# inv_sh_shoheil_74ls245.net
KiCad netlist of a schematic drawn in Altium Designer
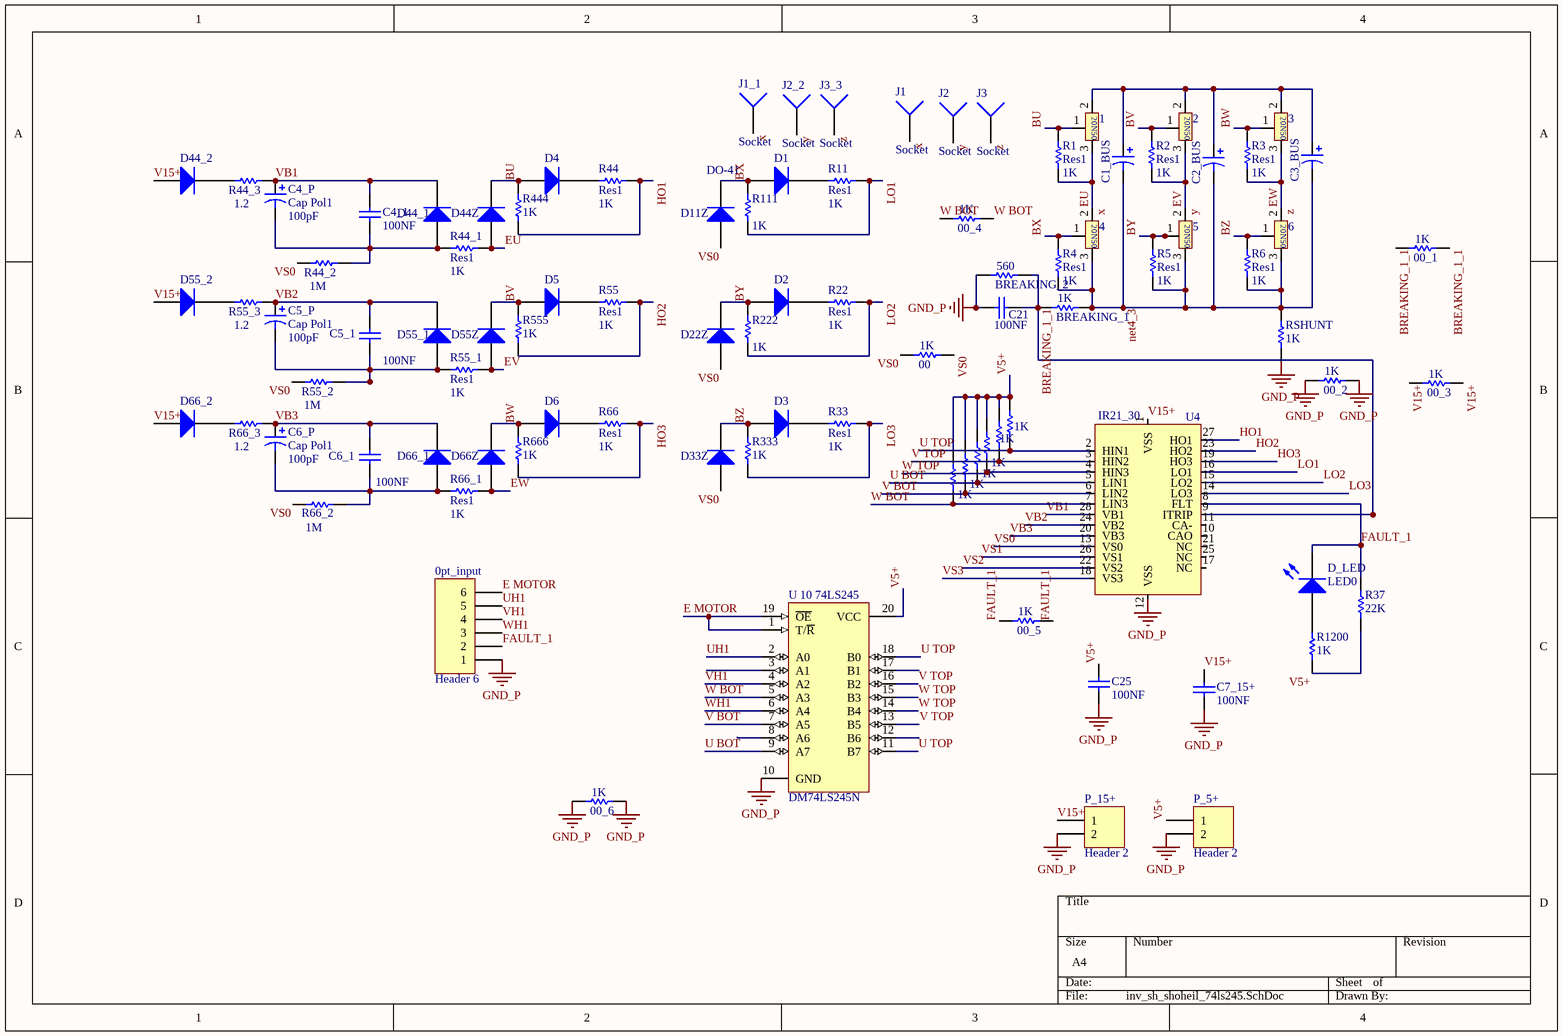
[diagram p0: inv_sh_shoheil_74ls245.SchDoc]

(export (version "E")
  (design (tool "Eeschema 10.0.6"))
  (components
    (comp (ref "00")
      (value "1K")
      (footprint "AXIAL-0.3")
      (description "Resistor")
      (fields (field (name "Comment") "Res1") (field (name "PUBLISHER") "Altium Limited"))
      (libsource (lib "Miscellaneous Devices") (part "Res1"))
    )
    (comp (ref "0pt_input")
      (value "Header 6")
      (footprint "HDR1X6")
      (description "Header, 6-Pin")
      (fields (field (name "PUBLISHER") "Altium Limited"))
      (libsource (lib "Miscellaneous Connectors") (part "Header 6"))
    )
    (comp (ref "00_1")
      (value "1K")
      (footprint "AXIAL-0.3")
      (description "Resistor")
      (fields (field (name "Comment") "Res1") (field (name "PUBLISHER") "Altium Limited"))
      (libsource (lib "Miscellaneous Devices") (part "Res1"))
    )
    (comp (ref "00_2")
      (value "1K")
      (footprint "AXIAL-0.3")
      (description "Resistor")
      (fields (field (name "Comment") "Res1") (field (name "PUBLISHER") "Altium Limited"))
      (libsource (lib "Miscellaneous Devices") (part "Res1"))
    )
    (comp (ref "00_3")
      (value "1K")
      (footprint "AXIAL-0.3")
      (description "Resistor")
      (fields (field (name "Comment") "Res1") (field (name "PUBLISHER") "Altium Limited"))
      (libsource (lib "Miscellaneous Devices") (part "Res1"))
    )
    (comp (ref "00_4")
      (value "1K")
      (footprint "AXIAL-0.3")
      (description "Resistor")
      (fields (field (name "Comment") "Res1") (field (name "PUBLISHER") "Altium Limited"))
      (libsource (lib "Miscellaneous Devices") (part "Res1"))
    )
    (comp (ref "00_5")
      (value "1K")
      (footprint "AXIAL-0.3")
      (description "Resistor")
      (fields (field (name "Comment") "Res1") (field (name "PUBLISHER") "Altium Limited"))
      (libsource (lib "Miscellaneous Devices") (part "Res1"))
    )
    (comp (ref "00_6")
      (value "1K")
      (footprint "AXIAL-0.3")
      (description "Resistor")
      (fields (field (name "Comment") "Res1") (field (name "PUBLISHER") "Altium Limited"))
      (libsource (lib "Miscellaneous Devices") (part "Res1"))
    )
    (comp (ref "1")
      (value "igbt_20n50")
      (footprint "20N50_S")
      (libsource (lib "INV_LIB_SH") (part "igbt_20n50"))
    )
    (comp (ref "2")
      (value "igbt_20n50")
      (footprint "20N50_S")
      (libsource (lib "INV_LIB_SH") (part "igbt_20n50"))
    )
    (comp (ref "3")
      (value "igbt_20n50")
      (footprint "20N50_S")
      (libsource (lib "INV_LIB_SH") (part "igbt_20n50"))
    )
    (comp (ref "4")
      (value "igbt_20n50")
      (footprint "20N50_S")
      (libsource (lib "INV_LIB_SH") (part "igbt_20n50"))
    )
    (comp (ref "5")
      (value "igbt_20n50")
      (footprint "20N50_S")
      (libsource (lib "INV_LIB_SH") (part "igbt_20n50"))
    )
    (comp (ref "6")
      (value "igbt_20n50")
      (footprint "20N50_S")
      (libsource (lib "INV_LIB_SH") (part "igbt_20n50"))
    )
    (comp (ref "BREAKING_1")
      (value "1K")
      (footprint "AXIAL-0.5")
      (description "Resistor")
      (fields (field (name "Comment") "Res1") (field (name "PUBLISHER") "Altium Limited"))
      (libsource (lib "Miscellaneous Devices") (part "Res1"))
    )
    (comp (ref "BREAKING_2")
      (value "560")
      (footprint "AXIAL-0.5")
      (description "Resistor")
      (fields (field (name "Comment") "Res1") (field (name "PUBLISHER") "Altium Limited"))
      (libsource (lib "Miscellaneous Devices") (part "Res1"))
    )
    (comp (ref "C1_BUS")
      (value "Cap Pol1")
      (footprint "RB7.6-15")
      (description "Polarized Capacitor (Radial)")
      (fields (field (name "PUBLISHER") "Altium Limited"))
      (libsource (lib "Miscellaneous Devices") (part "Cap Pol1"))
    )
    (comp (ref "C2_BUS")
      (value "Cap Pol1")
      (footprint "RB7.6-15")
      (description "Polarized Capacitor (Radial)")
      (fields (field (name "PUBLISHER") "Altium Limited"))
      (libsource (lib "Miscellaneous Devices") (part "Cap Pol1"))
    )
    (comp (ref "C3_BUS")
      (value "Cap Pol1")
      (footprint "RB7.6-15")
      (description "Polarized Capacitor (Radial)")
      (fields (field (name "PUBLISHER") "Altium Limited"))
      (libsource (lib "Miscellaneous Devices") (part "Cap Pol1"))
    )
    (comp (ref "C4_1")
      (value "100NF")
      (footprint "C2B")
      (description "Capacitor")
      (fields (field (name "Comment") "Cap") (field (name "PUBLISHER") "Altium Limited"))
      (libsource (lib "Miscellaneous Devices") (part "Cap"))
    )
    (comp (ref "C4_P")
      (value "Cap Pol1")
      (footprint "CE2")
      (description "Polarized Capacitor (Radial)")
      (fields (field (name "ALTIUM_VALUE") "100pF") (field (name "PUBLISHER") "Altium Limited"))
      (libsource (lib "Miscellaneous Devices") (part "Cap Pol1"))
    )
    (comp (ref "C5_1")
      (value "100NF")
      (footprint "C2B")
      (description "Capacitor")
      (fields (field (name "Comment") "Cap") (field (name "PUBLISHER") "Altium Limited"))
      (libsource (lib "Miscellaneous Devices") (part "Cap"))
    )
    (comp (ref "C5_P")
      (value "Cap Pol1")
      (footprint "CE2")
      (description "Polarized Capacitor (Radial)")
      (fields (field (name "ALTIUM_VALUE") "100pF") (field (name "PUBLISHER") "Altium Limited"))
      (libsource (lib "Miscellaneous Devices") (part "Cap Pol1"))
    )
    (comp (ref "C6_1")
      (value "100NF")
      (footprint "C2B")
      (description "Capacitor")
      (fields (field (name "Comment") "Cap") (field (name "PUBLISHER") "Altium Limited"))
      (libsource (lib "Miscellaneous Devices") (part "Cap"))
    )
    (comp (ref "C6_P")
      (value "Cap Pol1")
      (footprint "CE2")
      (description "Polarized Capacitor (Radial)")
      (fields (field (name "ALTIUM_VALUE") "100pF") (field (name "PUBLISHER") "Altium Limited"))
      (libsource (lib "Miscellaneous Devices") (part "Cap Pol1"))
    )
    (comp (ref "C7_15+")
      (value "100NF")
      (footprint "C2")
      (description "Capacitor")
      (fields (field (name "Comment") "Cap") (field (name "PUBLISHER") "Altium Limited"))
      (libsource (lib "Miscellaneous Devices") (part "Cap"))
    )
    (comp (ref "C21")
      (value "100NF")
      (footprint "C2")
      (description "Capacitor")
      (fields (field (name "Comment") "Cap") (field (name "PUBLISHER") "Altium Limited"))
      (libsource (lib "Miscellaneous Devices") (part "Cap"))
    )
    (comp (ref "C25")
      (value "100NF")
      (footprint "C2")
      (description "Capacitor")
      (fields (field (name "Comment") "Cap") (field (name "PUBLISHER") "Altium Limited"))
      (libsource (lib "Miscellaneous Devices") (part "Cap"))
    )
    (comp (ref "D1")
      (value "Diode 1N4007")
      (footprint "DIO10.46-5.3x2.8")
      (description "1 Amp General Purpose Rectifier")
      (fields (field (name "PUBLISHER") "Altium Limited"))
      (libsource (lib "Miscellaneous Devices") (part "Diode 1N4007"))
    )
    (comp (ref "D2")
      (value "Diode 1N4007")
      (footprint "DIO10.46-5.3x2.8")
      (description "1 Amp General Purpose Rectifier")
      (fields (field (name "PUBLISHER") "Altium Limited"))
      (libsource (lib "Miscellaneous Devices") (part "Diode 1N4007"))
    )
    (comp (ref "D3")
      (value "Diode 1N4007")
      (footprint "DIO10.46-5.3x2.8")
      (description "1 Amp General Purpose Rectifier")
      (fields (field (name "PUBLISHER") "Altium Limited"))
      (libsource (lib "Miscellaneous Devices") (part "Diode 1N4007"))
    )
    (comp (ref "D4")
      (value "Diode 1N4007")
      (footprint "DIO10.46-5.3x2.8")
      (description "1 Amp General Purpose Rectifier")
      (fields (field (name "PUBLISHER") "Altium Limited"))
      (libsource (lib "Miscellaneous Devices") (part "Diode 1N4007"))
    )
    (comp (ref "D5")
      (value "Diode 1N4007")
      (footprint "DIO10.46-5.3x2.8")
      (description "1 Amp General Purpose Rectifier")
      (fields (field (name "PUBLISHER") "Altium Limited"))
      (libsource (lib "Miscellaneous Devices") (part "Diode 1N4007"))
    )
    (comp (ref "D6")
      (value "Diode 1N4007")
      (footprint "DIO10.46-5.3x2.8")
      (description "1 Amp General Purpose Rectifier")
      (fields (field (name "PUBLISHER") "Altium Limited"))
      (libsource (lib "Miscellaneous Devices") (part "Diode 1N4007"))
    )
    (comp (ref "D11Z")
      (value "Diode 1N4007")
      (footprint "DIO10.46-5.3x2.8")
      (description "1 Amp General Purpose Rectifier")
      (fields (field (name "PACKAGEREFERENCE") "DO-41") (field (name "PUBLISHER") "Altium Limited"))
      (libsource (lib "Miscellaneous Devices") (part "Diode 1N4007"))
    )
    (comp (ref "D22Z")
      (value "Diode 1N4007")
      (footprint "DIO10.46-5.3x2.8")
      (description "1 Amp General Purpose Rectifier")
      (fields (field (name "PUBLISHER") "Altium Limited"))
      (libsource (lib "Miscellaneous Devices") (part "Diode 1N4007"))
    )
    (comp (ref "D33Z")
      (value "Diode 1N4007")
      (footprint "DIO10.46-5.3x2.8")
      (description "1 Amp General Purpose Rectifier")
      (fields (field (name "PUBLISHER") "Altium Limited"))
      (libsource (lib "Miscellaneous Devices") (part "Diode 1N4007"))
    )
    (comp (ref "D44Z")
      (value "Diode 1N4007")
      (footprint "DIO10.46-5.3x2.8")
      (description "1 Amp General Purpose Rectifier")
      (fields (field (name "PUBLISHER") "Altium Limited"))
      (libsource (lib "Miscellaneous Devices") (part "Diode 1N4007"))
    )
    (comp (ref "D44_1")
      (value "Diode 1N4007")
      (footprint "DIO10.46-5.3x2.8")
      (description "1 Amp General Purpose Rectifier")
      (fields (field (name "PUBLISHER") "Altium Limited"))
      (libsource (lib "Miscellaneous Devices") (part "Diode 1N4007"))
    )
    (comp (ref "D44_2")
      (value "Diode 1N4007")
      (footprint "DIO10.46-5.3x2.8")
      (description "1 Amp General Purpose Rectifier")
      (fields (field (name "PUBLISHER") "Altium Limited"))
      (libsource (lib "Miscellaneous Devices") (part "Diode 1N4007"))
    )
    (comp (ref "D55Z")
      (value "Diode 1N4007")
      (footprint "DIO10.46-5.3x2.8")
      (description "1 Amp General Purpose Rectifier")
      (fields (field (name "PUBLISHER") "Altium Limited"))
      (libsource (lib "Miscellaneous Devices") (part "Diode 1N4007"))
    )
    (comp (ref "D55_1")
      (value "Diode 1N4007")
      (footprint "DIO10.46-5.3x2.8")
      (description "1 Amp General Purpose Rectifier")
      (fields (field (name "PUBLISHER") "Altium Limited"))
      (libsource (lib "Miscellaneous Devices") (part "Diode 1N4007"))
    )
    (comp (ref "D55_2")
      (value "Diode 1N4007")
      (footprint "DIO10.46-5.3x2.8")
      (description "1 Amp General Purpose Rectifier")
      (fields (field (name "PUBLISHER") "Altium Limited"))
      (libsource (lib "Miscellaneous Devices") (part "Diode 1N4007"))
    )
    (comp (ref "D66Z")
      (value "Diode 1N4007")
      (footprint "DIO10.46-5.3x2.8")
      (description "1 Amp General Purpose Rectifier")
      (fields (field (name "PUBLISHER") "Altium Limited"))
      (libsource (lib "Miscellaneous Devices") (part "Diode 1N4007"))
    )
    (comp (ref "D66_1")
      (value "Diode 1N4007")
      (footprint "DIO10.46-5.3x2.8")
      (description "1 Amp General Purpose Rectifier")
      (fields (field (name "PUBLISHER") "Altium Limited"))
      (libsource (lib "Miscellaneous Devices") (part "Diode 1N4007"))
    )
    (comp (ref "D66_2")
      (value "Diode 1N4007")
      (footprint "DIO10.46-5.3x2.8")
      (description "1 Amp General Purpose Rectifier")
      (fields (field (name "PUBLISHER") "Altium Limited"))
      (libsource (lib "Miscellaneous Devices") (part "Diode 1N4007"))
    )
    (comp (ref "D_LED")
      (value "LED0")
      (footprint "CE5")
      (description "Typical INFRARED GaAs LED")
      (fields (field (name "PUBLISHER") "Altium Limited"))
      (libsource (lib "Miscellaneous Devices") (part "LED0"))
    )
    (comp (ref "J1")
      (value "Socket")
      (footprint "PIN1")
      (fields (field (name "PUBLISHER") "Altium Limited"))
      (libsource (lib "Miscellaneous Connectors") (part "Socket"))
    )
    (comp (ref "J1_1")
      (value "Socket")
      (footprint "PIN1")
      (fields (field (name "PUBLISHER") "Altium Limited"))
      (libsource (lib "Miscellaneous Connectors") (part "Socket"))
    )
    (comp (ref "J2")
      (value "Socket")
      (footprint "PIN1")
      (fields (field (name "PUBLISHER") "Altium Limited"))
      (libsource (lib "Miscellaneous Connectors") (part "Socket"))
    )
    (comp (ref "J2_2")
      (value "Socket")
      (footprint "PIN1")
      (fields (field (name "PUBLISHER") "Altium Limited"))
      (libsource (lib "Miscellaneous Connectors") (part "Socket"))
    )
    (comp (ref "J3")
      (value "Socket")
      (footprint "PIN1")
      (fields (field (name "PUBLISHER") "Altium Limited"))
      (libsource (lib "Miscellaneous Connectors") (part "Socket"))
    )
    (comp (ref "J3_3")
      (value "Socket")
      (footprint "PIN1")
      (fields (field (name "PUBLISHER") "Altium Limited"))
      (libsource (lib "Miscellaneous Connectors") (part "Socket"))
    )
    (comp (ref "P_5+")
      (value "Header 2")
      (footprint "HDR1X2")
      (description "Header, 2-Pin")
      (fields (field (name "PUBLISHER") "Altium Limited"))
      (libsource (lib "Miscellaneous Connectors") (part "Header 2"))
    )
    (comp (ref "P_15+")
      (value "Header 2")
      (footprint "HDR1X2")
      (description "Header, 2-Pin")
      (fields (field (name "PUBLISHER") "Altium Limited"))
      (libsource (lib "Miscellaneous Connectors") (part "Header 2"))
    )
    (comp (ref "R1")
      (value "Res1")
      (footprint "AXIAL-0.3")
      (description "Resistor")
      (fields (field (name "ALTIUM_VALUE") "1K") (field (name "PUBLISHER") "Altium Limited"))
      (libsource (lib "Miscellaneous Devices") (part "Res1"))
    )
    (comp (ref "R2")
      (value "Res1")
      (footprint "AXIAL-0.3")
      (description "Resistor")
      (fields (field (name "ALTIUM_VALUE") "1K") (field (name "PUBLISHER") "Altium Limited"))
      (libsource (lib "Miscellaneous Devices") (part "Res1"))
    )
    (comp (ref "R3")
      (value "Res1")
      (footprint "AXIAL-0.3")
      (description "Resistor")
      (fields (field (name "ALTIUM_VALUE") "1K") (field (name "PUBLISHER") "Altium Limited"))
      (libsource (lib "Miscellaneous Devices") (part "Res1"))
    )
    (comp (ref "R4")
      (value "Res1")
      (footprint "AXIAL-0.3")
      (description "Resistor")
      (fields (field (name "ALTIUM_VALUE") "1K") (field (name "PUBLISHER") "Altium Limited"))
      (libsource (lib "Miscellaneous Devices") (part "Res1"))
    )
    (comp (ref "R5")
      (value "Res1")
      (footprint "AXIAL-0.3")
      (description "Resistor")
      (fields (field (name "ALTIUM_VALUE") "1K") (field (name "PUBLISHER") "Altium Limited"))
      (libsource (lib "Miscellaneous Devices") (part "Res1"))
    )
    (comp (ref "R6")
      (value "Res1")
      (footprint "AXIAL-0.3")
      (description "Resistor")
      (fields (field (name "ALTIUM_VALUE") "1K") (field (name "PUBLISHER") "Altium Limited"))
      (libsource (lib "Miscellaneous Devices") (part "Res1"))
    )
    (comp (ref "R11")
      (value "Res1")
      (footprint "AXIAL-0.3")
      (description "Resistor")
      (fields (field (name "ALTIUM_VALUE") "1K") (field (name "PUBLISHER") "Altium Limited"))
      (libsource (lib "Miscellaneous Devices") (part "Res1"))
    )
    (comp (ref "R22")
      (value "Res1")
      (footprint "AXIAL-0.3")
      (description "Resistor")
      (fields (field (name "ALTIUM_VALUE") "1K") (field (name "PUBLISHER") "Altium Limited"))
      (libsource (lib "Miscellaneous Devices") (part "Res1"))
    )
    (comp (ref "R33")
      (value "Res1")
      (footprint "AXIAL-0.3")
      (description "Resistor")
      (fields (field (name "ALTIUM_VALUE") "1K") (field (name "PUBLISHER") "Altium Limited"))
      (libsource (lib "Miscellaneous Devices") (part "Res1"))
    )
    (comp (ref "R37")
      (value "22K")
      (footprint "AXIAL-0.3")
      (description "Resistor")
      (fields (field (name "Comment") "Res1") (field (name "PUBLISHER") "Altium Limited"))
      (libsource (lib "Miscellaneous Devices") (part "Res1"))
    )
    (comp (ref "R44")
      (value "Res1")
      (footprint "AXIAL-0.3")
      (description "Resistor")
      (fields (field (name "ALTIUM_VALUE") "1K") (field (name "PUBLISHER") "Altium Limited"))
      (libsource (lib "Miscellaneous Devices") (part "Res1"))
    )
    (comp (ref "R44_1")
      (value "Res1")
      (footprint "AXIAL-0.3")
      (description "Resistor")
      (fields (field (name "ALTIUM_VALUE") "1K") (field (name "PUBLISHER") "Altium Limited"))
      (libsource (lib "Miscellaneous Devices") (part "Res1"))
    )
    (comp (ref "R44_2")
      (value "1M")
      (footprint "AXIAL-0.3")
      (description "Resistor")
      (fields (field (name "Comment") "Res1") (field (name "PUBLISHER") "Altium Limited"))
      (libsource (lib "Miscellaneous Devices") (part "Res1"))
    )
    (comp (ref "R44_3")
      (value "1.2")
      (footprint "AXIAL-0.3")
      (description "Resistor")
      (fields (field (name "Comment") "Res1") (field (name "PUBLISHER") "Altium Limited"))
      (libsource (lib "Miscellaneous Devices") (part "Res1"))
    )
    (comp (ref "R47_1")
      (value "1K")
      (footprint "AXIAL-0.3")
      (description "Resistor")
      (fields (field (name "Comment") "Res1") (field (name "PUBLISHER") "Altium Limited"))
      (libsource (lib "Miscellaneous Devices") (part "Res1"))
    )
    (comp (ref "R47_2")
      (value "1K")
      (footprint "AXIAL-0.3")
      (description "Resistor")
      (fields (field (name "Comment") "Res1") (field (name "PUBLISHER") "Altium Limited"))
      (libsource (lib "Miscellaneous Devices") (part "Res1"))
    )
    (comp (ref "R47_3")
      (value "1K")
      (footprint "AXIAL-0.3")
      (description "Resistor")
      (fields (field (name "Comment") "Res1") (field (name "PUBLISHER") "Altium Limited"))
      (libsource (lib "Miscellaneous Devices") (part "Res1"))
    )
    (comp (ref "R47_4")
      (value "1K")
      (footprint "AXIAL-0.3")
      (description "Resistor")
      (fields (field (name "Comment") "Res1") (field (name "PUBLISHER") "Altium Limited"))
      (libsource (lib "Miscellaneous Devices") (part "Res1"))
    )
    (comp (ref "R47_5")
      (value "1K")
      (footprint "AXIAL-0.3")
      (description "Resistor")
      (fields (field (name "Comment") "Res1") (field (name "PUBLISHER") "Altium Limited"))
      (libsource (lib "Miscellaneous Devices") (part "Res1"))
    )
    (comp (ref "R47_6")
      (value "1K")
      (footprint "AXIAL-0.3")
      (description "Resistor")
      (fields (field (name "Comment") "Res1") (field (name "PUBLISHER") "Altium Limited"))
      (libsource (lib "Miscellaneous Devices") (part "Res1"))
    )
    (comp (ref "R55")
      (value "Res1")
      (footprint "AXIAL-0.3")
      (description "Resistor")
      (fields (field (name "ALTIUM_VALUE") "1K") (field (name "PUBLISHER") "Altium Limited"))
      (libsource (lib "Miscellaneous Devices") (part "Res1"))
    )
    (comp (ref "R55_1")
      (value "Res1")
      (footprint "AXIAL-0.3")
      (description "Resistor")
      (fields (field (name "ALTIUM_VALUE") "1K") (field (name "PUBLISHER") "Altium Limited"))
      (libsource (lib "Miscellaneous Devices") (part "Res1"))
    )
    (comp (ref "R55_2")
      (value "1M")
      (footprint "AXIAL-0.3")
      (description "Resistor")
      (fields (field (name "Comment") "Res1") (field (name "PUBLISHER") "Altium Limited"))
      (libsource (lib "Miscellaneous Devices") (part "Res1"))
    )
    (comp (ref "R55_3")
      (value "1.2")
      (footprint "AXIAL-0.3")
      (description "Resistor")
      (fields (field (name "Comment") "Res1") (field (name "PUBLISHER") "Altium Limited"))
      (libsource (lib "Miscellaneous Devices") (part "Res1"))
    )
    (comp (ref "R66")
      (value "Res1")
      (footprint "AXIAL-0.3")
      (description "Resistor")
      (fields (field (name "ALTIUM_VALUE") "1K") (field (name "PUBLISHER") "Altium Limited"))
      (libsource (lib "Miscellaneous Devices") (part "Res1"))
    )
    (comp (ref "R66_1")
      (value "Res1")
      (footprint "AXIAL-0.3")
      (description "Resistor")
      (fields (field (name "ALTIUM_VALUE") "1K") (field (name "PUBLISHER") "Altium Limited"))
      (libsource (lib "Miscellaneous Devices") (part "Res1"))
    )
    (comp (ref "R66_2")
      (value "1M")
      (footprint "AXIAL-0.3")
      (description "Resistor")
      (fields (field (name "Comment") "Res1") (field (name "PUBLISHER") "Altium Limited"))
      (libsource (lib "Miscellaneous Devices") (part "Res1"))
    )
    (comp (ref "R66_3")
      (value "1.2")
      (footprint "AXIAL-0.3")
      (description "Resistor")
      (fields (field (name "Comment") "Res1") (field (name "PUBLISHER") "Altium Limited"))
      (libsource (lib "Miscellaneous Devices") (part "Res1"))
    )
    (comp (ref "R111")
      (value "1K")
      (footprint "AXIAL-0.3")
      (description "Resistor")
      (fields (field (name "Comment") "Res1") (field (name "PUBLISHER") "Altium Limited"))
      (libsource (lib "Miscellaneous Devices") (part "Res1"))
    )
    (comp (ref "R222")
      (value "1K")
      (footprint "AXIAL-0.3")
      (description "Resistor")
      (fields (field (name "Comment") "Res1") (field (name "PUBLISHER") "Altium Limited"))
      (libsource (lib "Miscellaneous Devices") (part "Res1"))
    )
    (comp (ref "R333")
      (value "1K")
      (footprint "AXIAL-0.3")
      (description "Resistor")
      (fields (field (name "Comment") "Res1") (field (name "PUBLISHER") "Altium Limited"))
      (libsource (lib "Miscellaneous Devices") (part "Res1"))
    )
    (comp (ref "R444")
      (value "1K")
      (footprint "AXIAL-0.3")
      (description "Resistor")
      (fields (field (name "Comment") "Res1") (field (name "PUBLISHER") "Altium Limited"))
      (libsource (lib "Miscellaneous Devices") (part "Res1"))
    )
    (comp (ref "R555")
      (value "1K")
      (footprint "AXIAL-0.3")
      (description "Resistor")
      (fields (field (name "Comment") "Res1") (field (name "PUBLISHER") "Altium Limited"))
      (libsource (lib "Miscellaneous Devices") (part "Res1"))
    )
    (comp (ref "R666")
      (value "1K")
      (footprint "AXIAL-0.3")
      (description "Resistor")
      (fields (field (name "Comment") "Res1") (field (name "PUBLISHER") "Altium Limited"))
      (libsource (lib "Miscellaneous Devices") (part "Res1"))
    )
    (comp (ref "R1200")
      (value "1K")
      (footprint "AXIAL-0.3")
      (description "Resistor")
      (fields (field (name "Comment") "Res1") (field (name "PUBLISHER") "Altium Limited"))
      (libsource (lib "Miscellaneous Devices") (part "Res1"))
    )
    (comp (ref "RSHUNT")
      (value "1K")
      (footprint "AXIAL-1.0")
      (description "Resistor")
      (fields (field (name "Comment") "Res1") (field (name "PUBLISHER") "Altium Limited"))
      (libsource (lib "Miscellaneous Devices") (part "Res1"))
    )
    (comp (ref "U 10 74LS245")
      (value "DM74LS245N")
      (footprint "N20A")
      (description "3-State Octal Bus Transceiver")
      (fields (field (name "PUBLISHER") "Altium Limited"))
      (libsource (lib "FSC Interface Line Transceiver") (part "DM74LS245N"))
    )
    (comp (ref "U4") (value "IR21_30") (footprint "IR2130") (libsource (lib "IR2130_SH") (part "IR21_30")))
  )
  (nets
    (net (code "1") (name "/BREAKING_1_1") (class "Default")
      (node (ref "00_1") (pin "1") (pinfunction "1_1") (pintype "passive"))
      (node (ref "00_1") (pin "2") (pinfunction "2_2") (pintype "passive"))
      (node (ref "BREAKING_1") (pin "1") (pinfunction "1_1") (pintype "passive"))
      (node (ref "BREAKING_2") (pin "2") (pinfunction "2_2") (pintype "passive"))
      (node (ref "C21") (pin "1") (pinfunction "1_1") (pintype "passive"))
      (node (ref "U4") (pin "9") (pinfunction "ITRIP_9") (pintype "passive"))
    )
    (net (code "2") (name "/BU") (class "Default")
      (node (ref "1") (pin "1") (pinfunction "G_1") (pintype "passive"))
      (node (ref "D4") (pin "1") (pinfunction "A_1") (pintype "passive"))
      (node (ref "D44Z") (pin "2") (pinfunction "K_2") (pintype "passive"))
      (node (ref "R1") (pin "2") (pinfunction "2_2") (pintype "passive"))
      (node (ref "R444") (pin "2") (pinfunction "2_2") (pintype "passive"))
    )
    (net (code "3") (name "/BV") (class "Default")
      (node (ref "2") (pin "1") (pinfunction "G_1") (pintype "passive"))
      (node (ref "D5") (pin "1") (pinfunction "A_1") (pintype "passive"))
      (node (ref "D55Z") (pin "2") (pinfunction "K_2") (pintype "passive"))
      (node (ref "R2") (pin "2") (pinfunction "2_2") (pintype "passive"))
      (node (ref "R555") (pin "2") (pinfunction "2_2") (pintype "passive"))
    )
    (net (code "4") (name "/BW") (class "Default")
      (node (ref "3") (pin "1") (pinfunction "G_1") (pintype "passive"))
      (node (ref "D6") (pin "1") (pinfunction "A_1") (pintype "passive"))
      (node (ref "D66Z") (pin "2") (pinfunction "K_2") (pintype "passive"))
      (node (ref "R3") (pin "2") (pinfunction "2_2") (pintype "passive"))
      (node (ref "R666") (pin "2") (pinfunction "2_2") (pintype "passive"))
    )
    (net (code "5") (name "/BX") (class "Default")
      (node (ref "4") (pin "1") (pinfunction "G_1") (pintype "passive"))
      (node (ref "D1") (pin "1") (pinfunction "A_1") (pintype "passive"))
      (node (ref "D11Z") (pin "2") (pinfunction "K_2") (pintype "passive"))
      (node (ref "R111") (pin "2") (pinfunction "2_2") (pintype "passive"))
      (node (ref "R4") (pin "2") (pinfunction "2_2") (pintype "passive"))
    )
    (net (code "6") (name "/BY") (class "Default")
      (node (ref "5") (pin "1") (pinfunction "G_1") (pintype "passive"))
      (node (ref "D2") (pin "1") (pinfunction "A_1") (pintype "passive"))
      (node (ref "D22Z") (pin "2") (pinfunction "K_2") (pintype "passive"))
      (node (ref "R222") (pin "2") (pinfunction "2_2") (pintype "passive"))
      (node (ref "R5") (pin "2") (pinfunction "2_2") (pintype "passive"))
    )
    (net (code "7") (name "/BZ") (class "Default")
      (node (ref "6") (pin "1") (pinfunction "G_1") (pintype "passive"))
      (node (ref "D3") (pin "1") (pinfunction "A_1") (pintype "passive"))
      (node (ref "D33Z") (pin "2") (pinfunction "K_2") (pintype "passive"))
      (node (ref "R333") (pin "2") (pinfunction "2_2") (pintype "passive"))
      (node (ref "R6") (pin "2") (pinfunction "2_2") (pintype "passive"))
    )
    (net (code "8") (name "/E MOTOR") (class "Default")
      (node (ref "0pt_input") (pin "6") (pinfunction "6_6") (pintype "passive"))
      (node (ref "U 10 74LS245") (pin "1") (pinfunction "T/~{R}_1") (pintype "input"))
      (node (ref "U 10 74LS245") (pin "19") (pinfunction "~{OE}_19") (pintype "input"))
    )
    (net (code "9") (name "/EU") (class "Default")
      (node (ref "1") (pin "3") (pinfunction "E_3") (pintype "passive"))
      (node (ref "4") (pin "2") (pinfunction "C_2") (pintype "passive"))
      (node (ref "D44Z") (pin "1") (pinfunction "A_1") (pintype "passive"))
      (node (ref "J1") (pin "1") (pinfunction "1_1") (pintype "passive"))
      (node (ref "J1_1") (pin "1") (pinfunction "1_1") (pintype "passive"))
      (node (ref "R1") (pin "1") (pinfunction "1_1") (pintype "passive"))
      (node (ref "R44_1") (pin "2") (pinfunction "2_2") (pintype "passive"))
    )
    (net (code "10") (name "/EV") (class "Default")
      (node (ref "2") (pin "3") (pinfunction "E_3") (pintype "passive"))
      (node (ref "5") (pin "2") (pinfunction "C_2") (pintype "passive"))
      (node (ref "D55Z") (pin "1") (pinfunction "A_1") (pintype "passive"))
      (node (ref "J2") (pin "1") (pinfunction "1_1") (pintype "passive"))
      (node (ref "J2_2") (pin "1") (pinfunction "1_1") (pintype "passive"))
      (node (ref "R2") (pin "1") (pinfunction "1_1") (pintype "passive"))
      (node (ref "R55_1") (pin "2") (pinfunction "2_2") (pintype "passive"))
    )
    (net (code "11") (name "/EW") (class "Default")
      (node (ref "3") (pin "3") (pinfunction "E_3") (pintype "passive"))
      (node (ref "6") (pin "2") (pinfunction "C_2") (pintype "passive"))
      (node (ref "D66Z") (pin "1") (pinfunction "A_1") (pintype "passive"))
      (node (ref "J3") (pin "1") (pinfunction "1_1") (pintype "passive"))
      (node (ref "J3_3") (pin "1") (pinfunction "1_1") (pintype "passive"))
      (node (ref "R3") (pin "1") (pinfunction "1_1") (pintype "passive"))
      (node (ref "R66_1") (pin "2") (pinfunction "2_2") (pintype "passive"))
    )
    (net (code "12") (name "/FAULT_1") (class "Default")
      (node (ref "00_5") (pin "1") (pinfunction "1_1") (pintype "passive"))
      (node (ref "00_5") (pin "2") (pinfunction "2_2") (pintype "passive"))
      (node (ref "0pt_input") (pin "2") (pinfunction "2_2") (pintype "passive"))
      (node (ref "D_LED") (pin "2") (pinfunction "K_2") (pintype "passive"))
      (node (ref "R37") (pin "2") (pinfunction "2_2") (pintype "passive"))
      (node (ref "U4") (pin "8") (pinfunction "FLT_8") (pintype "passive"))
    )
    (net (code "13") (name "/HO1") (class "Default")
      (node (ref "R44") (pin "2") (pinfunction "2_2") (pintype "passive"))
      (node (ref "R444") (pin "1") (pinfunction "1_1") (pintype "passive"))
      (node (ref "U4") (pin "27") (pinfunction "HO1_27") (pintype "passive"))
    )
    (net (code "14") (name "/HO2") (class "Default")
      (node (ref "R55") (pin "2") (pinfunction "2_2") (pintype "passive"))
      (node (ref "R555") (pin "1") (pinfunction "1_1") (pintype "passive"))
      (node (ref "U4") (pin "23") (pinfunction "HO2_23") (pintype "passive"))
    )
    (net (code "15") (name "/HO3") (class "Default")
      (node (ref "R66") (pin "2") (pinfunction "2_2") (pintype "passive"))
      (node (ref "R666") (pin "1") (pinfunction "1_1") (pintype "passive"))
      (node (ref "U4") (pin "19") (pinfunction "HO3_19") (pintype "passive"))
    )
    (net (code "16") (name "/LO1") (class "Default")
      (node (ref "R11") (pin "2") (pinfunction "2_2") (pintype "passive"))
      (node (ref "R111") (pin "1") (pinfunction "1_1") (pintype "passive"))
      (node (ref "U4") (pin "16") (pinfunction "LO1_16") (pintype "passive"))
    )
    (net (code "17") (name "/LO2") (class "Default")
      (node (ref "R22") (pin "2") (pinfunction "2_2") (pintype "passive"))
      (node (ref "R222") (pin "1") (pinfunction "1_1") (pintype "passive"))
      (node (ref "U4") (pin "15") (pinfunction "LO2_15") (pintype "passive"))
    )
    (net (code "18") (name "/LO3") (class "Default")
      (node (ref "R33") (pin "2") (pinfunction "2_2") (pintype "passive"))
      (node (ref "R333") (pin "1") (pinfunction "1_1") (pintype "passive"))
      (node (ref "U4") (pin "14") (pinfunction "LO3_14") (pintype "passive"))
    )
    (net (code "19") (name "/U BOT") (class "Default")
      (node (ref "R47_4") (pin "2") (pinfunction "2_2") (pintype "passive"))
      (node (ref "U 10 74LS245") (pin "9") (pinfunction "A7_9") (pintype "bidirectional"))
      (node (ref "U4") (pin "5") (pinfunction "LIN1_5") (pintype "passive"))
    )
    (net (code "20") (name "/U TOP") (class "Default")
      (node (ref "R47_1") (pin "2") (pinfunction "2_2") (pintype "passive"))
      (node (ref "U 10 74LS245") (pin "11") (pinfunction "B7_11") (pintype "bidirectional"))
      (node (ref "U 10 74LS245") (pin "18") (pinfunction "B0_18") (pintype "bidirectional"))
      (node (ref "U4") (pin "2") (pinfunction "HIN1_2") (pintype "passive"))
    )
    (net (code "21") (name "/UH1") (class "Default")
      (node (ref "0pt_input") (pin "5") (pinfunction "5_5") (pintype "passive"))
      (node (ref "U 10 74LS245") (pin "2") (pinfunction "A0_2") (pintype "bidirectional"))
    )
    (net (code "22") (name "/V BOT") (class "Default")
      (node (ref "R47_5") (pin "2") (pinfunction "2_2") (pintype "passive"))
      (node (ref "U 10 74LS245") (pin "7") (pinfunction "A5_7") (pintype "bidirectional"))
      (node (ref "U4") (pin "6") (pinfunction "LIN2_6") (pintype "passive"))
    )
    (net (code "23") (name "/V TOP") (class "Default")
      (node (ref "R47_2") (pin "2") (pinfunction "2_2") (pintype "passive"))
      (node (ref "U 10 74LS245") (pin "13") (pinfunction "B5_13") (pintype "bidirectional"))
      (node (ref "U 10 74LS245") (pin "16") (pinfunction "B2_16") (pintype "bidirectional"))
      (node (ref "U4") (pin "3") (pinfunction "HIN2_3") (pintype "passive"))
    )
    (net (code "24") (name "/V5+") (class "Default")
      (node (ref "C25") (pin "1") (pinfunction "1_1") (pintype "passive"))
      (node (ref "P_5+") (pin "1") (pinfunction "1_1") (pintype "passive"))
      (node (ref "R1200") (pin "1") (pinfunction "1_1") (pintype "passive"))
      (node (ref "R37") (pin "1") (pinfunction "1_1") (pintype "passive"))
      (node (ref "R47_1") (pin "1") (pinfunction "1_1") (pintype "passive"))
      (node (ref "R47_2") (pin "1") (pinfunction "1_1") (pintype "passive"))
      (node (ref "R47_3") (pin "1") (pinfunction "1_1") (pintype "passive"))
      (node (ref "R47_4") (pin "1") (pinfunction "1_1") (pintype "passive"))
      (node (ref "R47_5") (pin "1") (pinfunction "1_1") (pintype "passive"))
      (node (ref "R47_6") (pin "1") (pinfunction "1_1") (pintype "passive"))
      (node (ref "U 10 74LS245") (pin "20") (pinfunction "VCC_20") (pintype "power_in"))
    )
    (net (code "25") (name "/V15+") (class "Default")
      (node (ref "00_3") (pin "1") (pinfunction "1_1") (pintype "passive"))
      (node (ref "00_3") (pin "2") (pinfunction "2_2") (pintype "passive"))
      (node (ref "C7_15+") (pin "1") (pinfunction "1_1") (pintype "passive"))
      (node (ref "D44_2") (pin "1") (pinfunction "A_1") (pintype "passive"))
      (node (ref "D55_2") (pin "1") (pinfunction "A_1") (pintype "passive"))
      (node (ref "D66_2") (pin "1") (pinfunction "A_1") (pintype "passive"))
      (node (ref "P_15+") (pin "1") (pinfunction "1_1") (pintype "passive"))
      (node (ref "U4") (pin "1") (pinfunction "VSS_1") (pintype "passive"))
    )
    (net (code "26") (name "/VB1") (class "Default")
      (node (ref "C4_1") (pin "2") (pinfunction "2_2") (pintype "passive"))
      (node (ref "C4_P") (pin "1") (pinfunction "1_1") (pintype "passive"))
      (node (ref "D44_1") (pin "2") (pinfunction "K_2") (pintype "passive"))
      (node (ref "R44_3") (pin "2") (pinfunction "2_2") (pintype "passive"))
      (node (ref "U4") (pin "28") (pinfunction "VB1_28") (pintype "passive"))
    )
    (net (code "27") (name "/VB2") (class "Default")
      (node (ref "C5_1") (pin "2") (pinfunction "2_2") (pintype "passive"))
      (node (ref "C5_P") (pin "1") (pinfunction "1_1") (pintype "passive"))
      (node (ref "D55_1") (pin "2") (pinfunction "K_2") (pintype "passive"))
      (node (ref "R55_3") (pin "2") (pinfunction "2_2") (pintype "passive"))
      (node (ref "U4") (pin "24") (pinfunction "VB2_24") (pintype "passive"))
    )
    (net (code "28") (name "/VB3") (class "Default")
      (node (ref "C6_1") (pin "2") (pinfunction "2_2") (pintype "passive"))
      (node (ref "C6_P") (pin "1") (pinfunction "1_1") (pintype "passive"))
      (node (ref "D66_1") (pin "2") (pinfunction "K_2") (pintype "passive"))
      (node (ref "R66_3") (pin "2") (pinfunction "2_2") (pintype "passive"))
      (node (ref "U4") (pin "20") (pinfunction "VB3_20") (pintype "passive"))
    )
    (net (code "29") (name "/VH1") (class "Default")
      (node (ref "0pt_input") (pin "4") (pinfunction "4_4") (pintype "passive"))
      (node (ref "U 10 74LS245") (pin "4") (pinfunction "A2_4") (pintype "bidirectional"))
    )
    (net (code "30") (name "/VS0") (class "Default")
      (node (ref "00") (pin "1") (pinfunction "1_1") (pintype "passive"))
      (node (ref "00") (pin "2") (pinfunction "2_2") (pintype "passive"))
      (node (ref "D11Z") (pin "1") (pinfunction "A_1") (pintype "passive"))
      (node (ref "D22Z") (pin "1") (pinfunction "A_1") (pintype "passive"))
      (node (ref "D33Z") (pin "1") (pinfunction "A_1") (pintype "passive"))
      (node (ref "R44_2") (pin "1") (pinfunction "1_1") (pintype "passive"))
      (node (ref "R55_2") (pin "1") (pinfunction "1_1") (pintype "passive"))
      (node (ref "R66_2") (pin "1") (pinfunction "1_1") (pintype "passive"))
      (node (ref "U4") (pin "13") (pinfunction "VS0_13") (pintype "passive"))
    )
    (net (code "31") (name "/VS1") (class "Default")
      (node (ref "U4") (pin "26") (pinfunction "VS1_26") (pintype "passive"))
    )
    (net (code "32") (name "/VS2") (class "Default")
      (node (ref "U4") (pin "22") (pinfunction "VS2_22") (pintype "passive"))
    )
    (net (code "33") (name "/VS3") (class "Default")
      (node (ref "U4") (pin "18") (pinfunction "VS3_18") (pintype "passive"))
    )
    (net (code "34") (name "/W BOT") (class "Default")
      (node (ref "00_4") (pin "1") (pinfunction "1_1") (pintype "passive"))
      (node (ref "00_4") (pin "2") (pinfunction "2_2") (pintype "passive"))
      (node (ref "R47_6") (pin "2") (pinfunction "2_2") (pintype "passive"))
      (node (ref "U 10 74LS245") (pin "5") (pinfunction "A3_5") (pintype "bidirectional"))
      (node (ref "U4") (pin "7") (pinfunction "LIN3_7") (pintype "passive"))
    )
    (net (code "35") (name "/W TOP") (class "Default")
      (node (ref "R47_3") (pin "2") (pinfunction "2_2") (pintype "passive"))
      (node (ref "U 10 74LS245") (pin "14") (pinfunction "B4_14") (pintype "bidirectional"))
      (node (ref "U 10 74LS245") (pin "15") (pinfunction "B3_15") (pintype "bidirectional"))
      (node (ref "U4") (pin "4") (pinfunction "HIN3_4") (pintype "passive"))
    )
    (net (code "36") (name "/WH1") (class "Default")
      (node (ref "0pt_input") (pin "3") (pinfunction "3_3") (pintype "passive"))
      (node (ref "U 10 74LS245") (pin "6") (pinfunction "A4_6") (pintype "bidirectional"))
    )
    (net (code "37") (name "/net4_3") (class "Default")
      (node (ref "4") (pin "3") (pinfunction "E_3") (pintype "passive"))
      (node (ref "5") (pin "3") (pinfunction "E_3") (pintype "passive"))
      (node (ref "6") (pin "3") (pinfunction "E_3") (pintype "passive"))
      (node (ref "BREAKING_1") (pin "2") (pinfunction "2_2") (pintype "passive"))
      (node (ref "C1_BUS") (pin "2") (pinfunction "2_2") (pintype "passive"))
      (node (ref "C2_BUS") (pin "2") (pinfunction "2_2") (pintype "passive"))
      (node (ref "C3_BUS") (pin "2") (pinfunction "2_2") (pintype "passive"))
      (node (ref "R4") (pin "1") (pinfunction "1_1") (pintype "passive"))
      (node (ref "R5") (pin "1") (pinfunction "1_1") (pintype "passive"))
      (node (ref "R6") (pin "1") (pinfunction "1_1") (pintype "passive"))
      (node (ref "RSHUNT") (pin "2") (pinfunction "2_2") (pintype "passive"))
    )
    (net (code "38") (name "GND_P") (class "Default")
      (node (ref "00_2") (pin "1") (pinfunction "1_1") (pintype "passive"))
      (node (ref "00_2") (pin "2") (pinfunction "2_2") (pintype "passive"))
      (node (ref "00_6") (pin "1") (pinfunction "1_1") (pintype "passive"))
      (node (ref "00_6") (pin "2") (pinfunction "2_2") (pintype "passive"))
      (node (ref "0pt_input") (pin "1") (pinfunction "1_1") (pintype "passive"))
      (node (ref "BREAKING_2") (pin "1") (pinfunction "1_1") (pintype "passive"))
      (node (ref "C21") (pin "2") (pinfunction "2_2") (pintype "passive"))
      (node (ref "C25") (pin "2") (pinfunction "2_2") (pintype "passive"))
      (node (ref "C7_15+") (pin "2") (pinfunction "2_2") (pintype "passive"))
      (node (ref "P_15+") (pin "2") (pinfunction "2_2") (pintype "passive"))
      (node (ref "P_5+") (pin "2") (pinfunction "2_2") (pintype "passive"))
      (node (ref "RSHUNT") (pin "1") (pinfunction "1_1") (pintype "passive"))
      (node (ref "U 10 74LS245") (pin "10") (pinfunction "GND_10") (pintype "power_in"))
      (node (ref "U4") (pin "12") (pinfunction "VSS_12") (pintype "passive"))
    )
    (net (code "39") (name "Net-(1-C)") (class "Default")
      (node (ref "1") (pin "2") (pinfunction "C_2") (pintype "passive"))
      (node (ref "2") (pin "2") (pinfunction "C_2") (pintype "passive"))
      (node (ref "3") (pin "2") (pinfunction "C_2") (pintype "passive"))
      (node (ref "C1_BUS") (pin "1") (pinfunction "1_1") (pintype "passive"))
      (node (ref "C2_BUS") (pin "1") (pinfunction "1_1") (pintype "passive"))
      (node (ref "C3_BUS") (pin "1") (pinfunction "1_1") (pintype "passive"))
    )
    (net (code "40") (name "Net-(D1-K)") (class "Default")
      (node (ref "D1") (pin "2") (pinfunction "K_2") (pintype "passive"))
      (node (ref "R11") (pin "1") (pinfunction "1_1") (pintype "passive"))
    )
    (net (code "41") (name "Net-(D2-K)") (class "Default")
      (node (ref "D2") (pin "2") (pinfunction "K_2") (pintype "passive"))
      (node (ref "R22") (pin "1") (pinfunction "1_1") (pintype "passive"))
    )
    (net (code "42") (name "Net-(D3-K)") (class "Default")
      (node (ref "D3") (pin "2") (pinfunction "K_2") (pintype "passive"))
      (node (ref "R33") (pin "1") (pinfunction "1_1") (pintype "passive"))
    )
    (net (code "43") (name "Net-(D4-K)") (class "Default")
      (node (ref "D4") (pin "2") (pinfunction "K_2") (pintype "passive"))
      (node (ref "R44") (pin "1") (pinfunction "1_1") (pintype "passive"))
    )
    (net (code "44") (name "Net-(D5-K)") (class "Default")
      (node (ref "D5") (pin "2") (pinfunction "K_2") (pintype "passive"))
      (node (ref "R55") (pin "1") (pinfunction "1_1") (pintype "passive"))
    )
    (net (code "45") (name "Net-(D6-K)") (class "Default")
      (node (ref "D6") (pin "2") (pinfunction "K_2") (pintype "passive"))
      (node (ref "R66") (pin "1") (pinfunction "1_1") (pintype "passive"))
    )
    (net (code "46") (name "Net-(D44_1-A)") (class "Default")
      (node (ref "C4_1") (pin "1") (pinfunction "1_1") (pintype "passive"))
      (node (ref "C4_P") (pin "2") (pinfunction "2_2") (pintype "passive"))
      (node (ref "D44_1") (pin "1") (pinfunction "A_1") (pintype "passive"))
      (node (ref "R44_1") (pin "1") (pinfunction "1_1") (pintype "passive"))
      (node (ref "R44_2") (pin "2") (pinfunction "2_2") (pintype "passive"))
    )
    (net (code "47") (name "Net-(D44_2-K)") (class "Default")
      (node (ref "D44_2") (pin "2") (pinfunction "K_2") (pintype "passive"))
      (node (ref "R44_3") (pin "1") (pinfunction "1_1") (pintype "passive"))
    )
    (net (code "48") (name "Net-(D55_1-A)") (class "Default")
      (node (ref "C5_1") (pin "1") (pinfunction "1_1") (pintype "passive"))
      (node (ref "C5_P") (pin "2") (pinfunction "2_2") (pintype "passive"))
      (node (ref "D55_1") (pin "1") (pinfunction "A_1") (pintype "passive"))
      (node (ref "R55_1") (pin "1") (pinfunction "1_1") (pintype "passive"))
      (node (ref "R55_2") (pin "2") (pinfunction "2_2") (pintype "passive"))
    )
    (net (code "49") (name "Net-(D55_2-K)") (class "Default")
      (node (ref "D55_2") (pin "2") (pinfunction "K_2") (pintype "passive"))
      (node (ref "R55_3") (pin "1") (pinfunction "1_1") (pintype "passive"))
    )
    (net (code "50") (name "Net-(D66_1-A)") (class "Default")
      (node (ref "C6_1") (pin "1") (pinfunction "1_1") (pintype "passive"))
      (node (ref "C6_P") (pin "2") (pinfunction "2_2") (pintype "passive"))
      (node (ref "D66_1") (pin "1") (pinfunction "A_1") (pintype "passive"))
      (node (ref "R66_1") (pin "1") (pinfunction "1_1") (pintype "passive"))
      (node (ref "R66_2") (pin "2") (pinfunction "2_2") (pintype "passive"))
    )
    (net (code "51") (name "Net-(D66_2-K)") (class "Default")
      (node (ref "D66_2") (pin "2") (pinfunction "K_2") (pintype "passive"))
      (node (ref "R66_3") (pin "1") (pinfunction "1_1") (pintype "passive"))
    )
    (net (code "52") (name "Net-(D_LED-A)") (class "Default")
      (node (ref "D_LED") (pin "1") (pinfunction "A_1") (pintype "passive"))
      (node (ref "R1200") (pin "2") (pinfunction "2_2") (pintype "passive"))
    )
    (net (code "53") (name "unconnected-(U 10 74LS245-A1-Pad3)") (class "Default")
      (node (ref "U 10 74LS245") (pin "3") (pinfunction "A1_3") (pintype "bidirectional"))
    )
    (net (code "54") (name "unconnected-(U 10 74LS245-A6-Pad8)") (class "Default")
      (node (ref "U 10 74LS245") (pin "8") (pinfunction "A6_8") (pintype "bidirectional"))
    )
    (net (code "55") (name "unconnected-(U 10 74LS245-B1-Pad17)") (class "Default")
      (node (ref "U 10 74LS245") (pin "17") (pinfunction "B1_17") (pintype "bidirectional"))
    )
    (net (code "56") (name "unconnected-(U 10 74LS245-B6-Pad12)") (class "Default")
      (node (ref "U 10 74LS245") (pin "12") (pinfunction "B6_12") (pintype "bidirectional"))
    )
    (net (code "57") (name "unconnected-(U4-CA--Pad11)") (class "Default")
      (node (ref "U4") (pin "11") (pinfunction "CA-_11") (pintype "passive"))
    )
    (net (code "58") (name "unconnected-(U4-CAO-Pad10)") (class "Default")
      (node (ref "U4") (pin "10") (pinfunction "CAO_10") (pintype "passive"))
    )
    (net (code "59") (name "unconnected-(U4-NC-Pad17)") (class "Default")
      (node (ref "U4") (pin "17") (pinfunction "NC_17") (pintype "passive"))
    )
    (net (code "60") (name "unconnected-(U4-NC-Pad21)") (class "Default")
      (node (ref "U4") (pin "21") (pinfunction "NC_21") (pintype "passive"))
    )
    (net (code "61") (name "unconnected-(U4-NC-Pad25)") (class "Default")
      (node (ref "U4") (pin "25") (pinfunction "NC_25") (pintype "passive"))
    )
  )
)
